# Inputs.net
KiCad netlist of a schematic drawn in Altium Designer
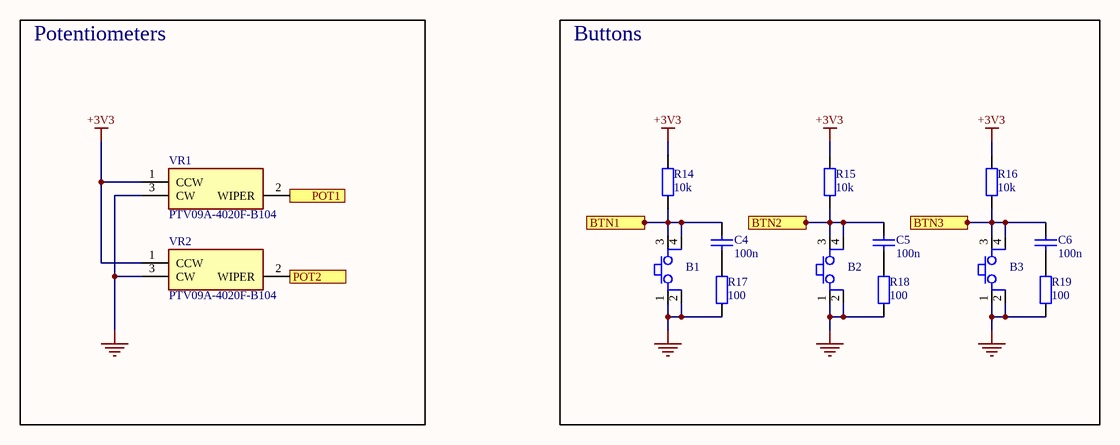
[diagram p0: Inputs.SchDoc]

(export (version "E")
  (design (tool "Eeschema 10.0.6"))
  (components
    (comp (ref "B1")
      (value "FSM4JSMA")
      (footprint "FP_BTN_SMD")
      (description "Tactile Switch")
      (libsource (lib "hallglib") (part "Button 4P"))
    )
    (comp (ref "B2")
      (value "FSM4JSMA")
      (footprint "FP_BTN_SMD")
      (description "Tactile Switch")
      (libsource (lib "hallglib") (part "Button 4P"))
    )
    (comp (ref "B3")
      (value "FSM4JSMA")
      (footprint "FP_BTN_SMD")
      (description "Tactile Switch")
      (libsource (lib "hallglib") (part "Button 4P"))
    )
    (comp (ref "C4")
      (value "100n")
      (footprint "FP_0805_CAP_085")
      (description "Capacitor")
      (libsource (lib "hallglib") (part "CAP"))
    )
    (comp (ref "C5")
      (value "100n")
      (footprint "FP_0805_CAP_085")
      (description "Capacitor")
      (libsource (lib "hallglib") (part "CAP"))
    )
    (comp (ref "C6")
      (value "100n")
      (footprint "FP_0805_CAP_085")
      (description "Capacitor")
      (libsource (lib "hallglib") (part "CAP"))
    )
    (comp (ref "R14")
      (value "10k")
      (footprint "FP_0805_RES")
      (description "Resistor")
      (libsource (lib "hallglib") (part "RES"))
    )
    (comp (ref "R15")
      (value "10k")
      (footprint "FP_0805_RES")
      (description "Resistor")
      (libsource (lib "hallglib") (part "RES"))
    )
    (comp (ref "R16")
      (value "10k")
      (footprint "FP_0805_RES")
      (description "Resistor")
      (libsource (lib "hallglib") (part "RES"))
    )
    (comp (ref "R17")
      (value "100")
      (footprint "FP_0805_RES")
      (description "Resistor")
      (libsource (lib "hallglib") (part "RES"))
    )
    (comp (ref "R18")
      (value "100")
      (footprint "FP_0805_RES")
      (description "Resistor")
      (libsource (lib "hallglib") (part "RES"))
    )
    (comp (ref "R19")
      (value "100")
      (footprint "FP_0805_RES")
      (description "Resistor")
      (libsource (lib "hallglib") (part "RES"))
    )
    (comp (ref "VR1")
      (value "PTV09A-4020F-B104")
      (footprint "SamacSys:PTV09A4020FB103")
      (description "Variable Resistor")
      (libsource (lib "SamacSys") (part "PTV09A-4020F-B104"))
    )
    (comp (ref "VR2")
      (value "PTV09A-4020F-B104")
      (footprint "SamacSys:PTV09A4020FB103")
      (description "Variable Resistor")
      (libsource (lib "SamacSys") (part "PTV09A-4020F-B104"))
    )
  )
  (nets
    (net (code "1") (name "+3V3") (class "Default")
      (node (ref "R14") (pin "2") (pinfunction "2_2") (pintype "passive"))
      (node (ref "R15") (pin "2") (pinfunction "2_2") (pintype "passive"))
      (node (ref "R16") (pin "2") (pinfunction "2_2") (pintype "passive"))
      (node (ref "VR1") (pin "1") (pinfunction "CCW_1") (pintype "passive"))
      (node (ref "VR2") (pin "1") (pinfunction "CCW_1") (pintype "passive"))
    )
    (net (code "2") (name "/BTN1") (class "Default")
      (node (ref "B1") (pin "3") (pinfunction "3_3") (pintype "passive"))
      (node (ref "B1") (pin "4") (pinfunction "4_4") (pintype "passive"))
      (node (ref "C4") (pin "1") (pinfunction "1_1") (pintype "passive"))
      (node (ref "R14") (pin "1") (pinfunction "1_1") (pintype "passive"))
    )
    (net (code "3") (name "/BTN2") (class "Default")
      (node (ref "B2") (pin "3") (pinfunction "3_3") (pintype "passive"))
      (node (ref "B2") (pin "4") (pinfunction "4_4") (pintype "passive"))
      (node (ref "C5") (pin "1") (pinfunction "1_1") (pintype "passive"))
      (node (ref "R15") (pin "1") (pinfunction "1_1") (pintype "passive"))
    )
    (net (code "4") (name "/BTN3") (class "Default")
      (node (ref "B3") (pin "3") (pinfunction "3_3") (pintype "passive"))
      (node (ref "B3") (pin "4") (pinfunction "4_4") (pintype "passive"))
      (node (ref "C6") (pin "1") (pinfunction "1_1") (pintype "passive"))
      (node (ref "R16") (pin "1") (pinfunction "1_1") (pintype "passive"))
    )
    (net (code "5") (name "/POT1") (class "Default")
      (node (ref "VR1") (pin "2") (pinfunction "WIPER_2") (pintype "passive"))
    )
    (net (code "6") (name "/POT2") (class "Default")
      (node (ref "VR2") (pin "2") (pinfunction "WIPER_2") (pintype "passive"))
    )
    (net (code "7") (name "GND") (class "Default")
      (node (ref "B1") (pin "1") (pinfunction "1_1") (pintype "passive"))
      (node (ref "B1") (pin "2") (pinfunction "2_2") (pintype "passive"))
      (node (ref "B2") (pin "1") (pinfunction "1_1") (pintype "passive"))
      (node (ref "B2") (pin "2") (pinfunction "2_2") (pintype "passive"))
      (node (ref "B3") (pin "1") (pinfunction "1_1") (pintype "passive"))
      (node (ref "B3") (pin "2") (pinfunction "2_2") (pintype "passive"))
      (node (ref "R17") (pin "1") (pinfunction "1_1") (pintype "passive"))
      (node (ref "R18") (pin "1") (pinfunction "1_1") (pintype "passive"))
      (node (ref "R19") (pin "1") (pinfunction "1_1") (pintype "passive"))
      (node (ref "VR1") (pin "3") (pinfunction "CW_3") (pintype "passive"))
      (node (ref "VR2") (pin "3") (pinfunction "CW_3") (pintype "passive"))
    )
    (net (code "8") (name "Net-(C4-Pad2)") (class "Default")
      (node (ref "C4") (pin "2") (pinfunction "2_2") (pintype "passive"))
      (node (ref "R17") (pin "2") (pinfunction "2_2") (pintype "passive"))
    )
    (net (code "9") (name "Net-(C5-Pad2)") (class "Default")
      (node (ref "C5") (pin "2") (pinfunction "2_2") (pintype "passive"))
      (node (ref "R18") (pin "2") (pinfunction "2_2") (pintype "passive"))
    )
    (net (code "10") (name "Net-(C6-Pad2)") (class "Default")
      (node (ref "C6") (pin "2") (pinfunction "2_2") (pintype "passive"))
      (node (ref "R19") (pin "2") (pinfunction "2_2") (pintype "passive"))
    )
  )
)
